# V1_1.net
KiCad netlist of a schematic drawn in Altium Designer
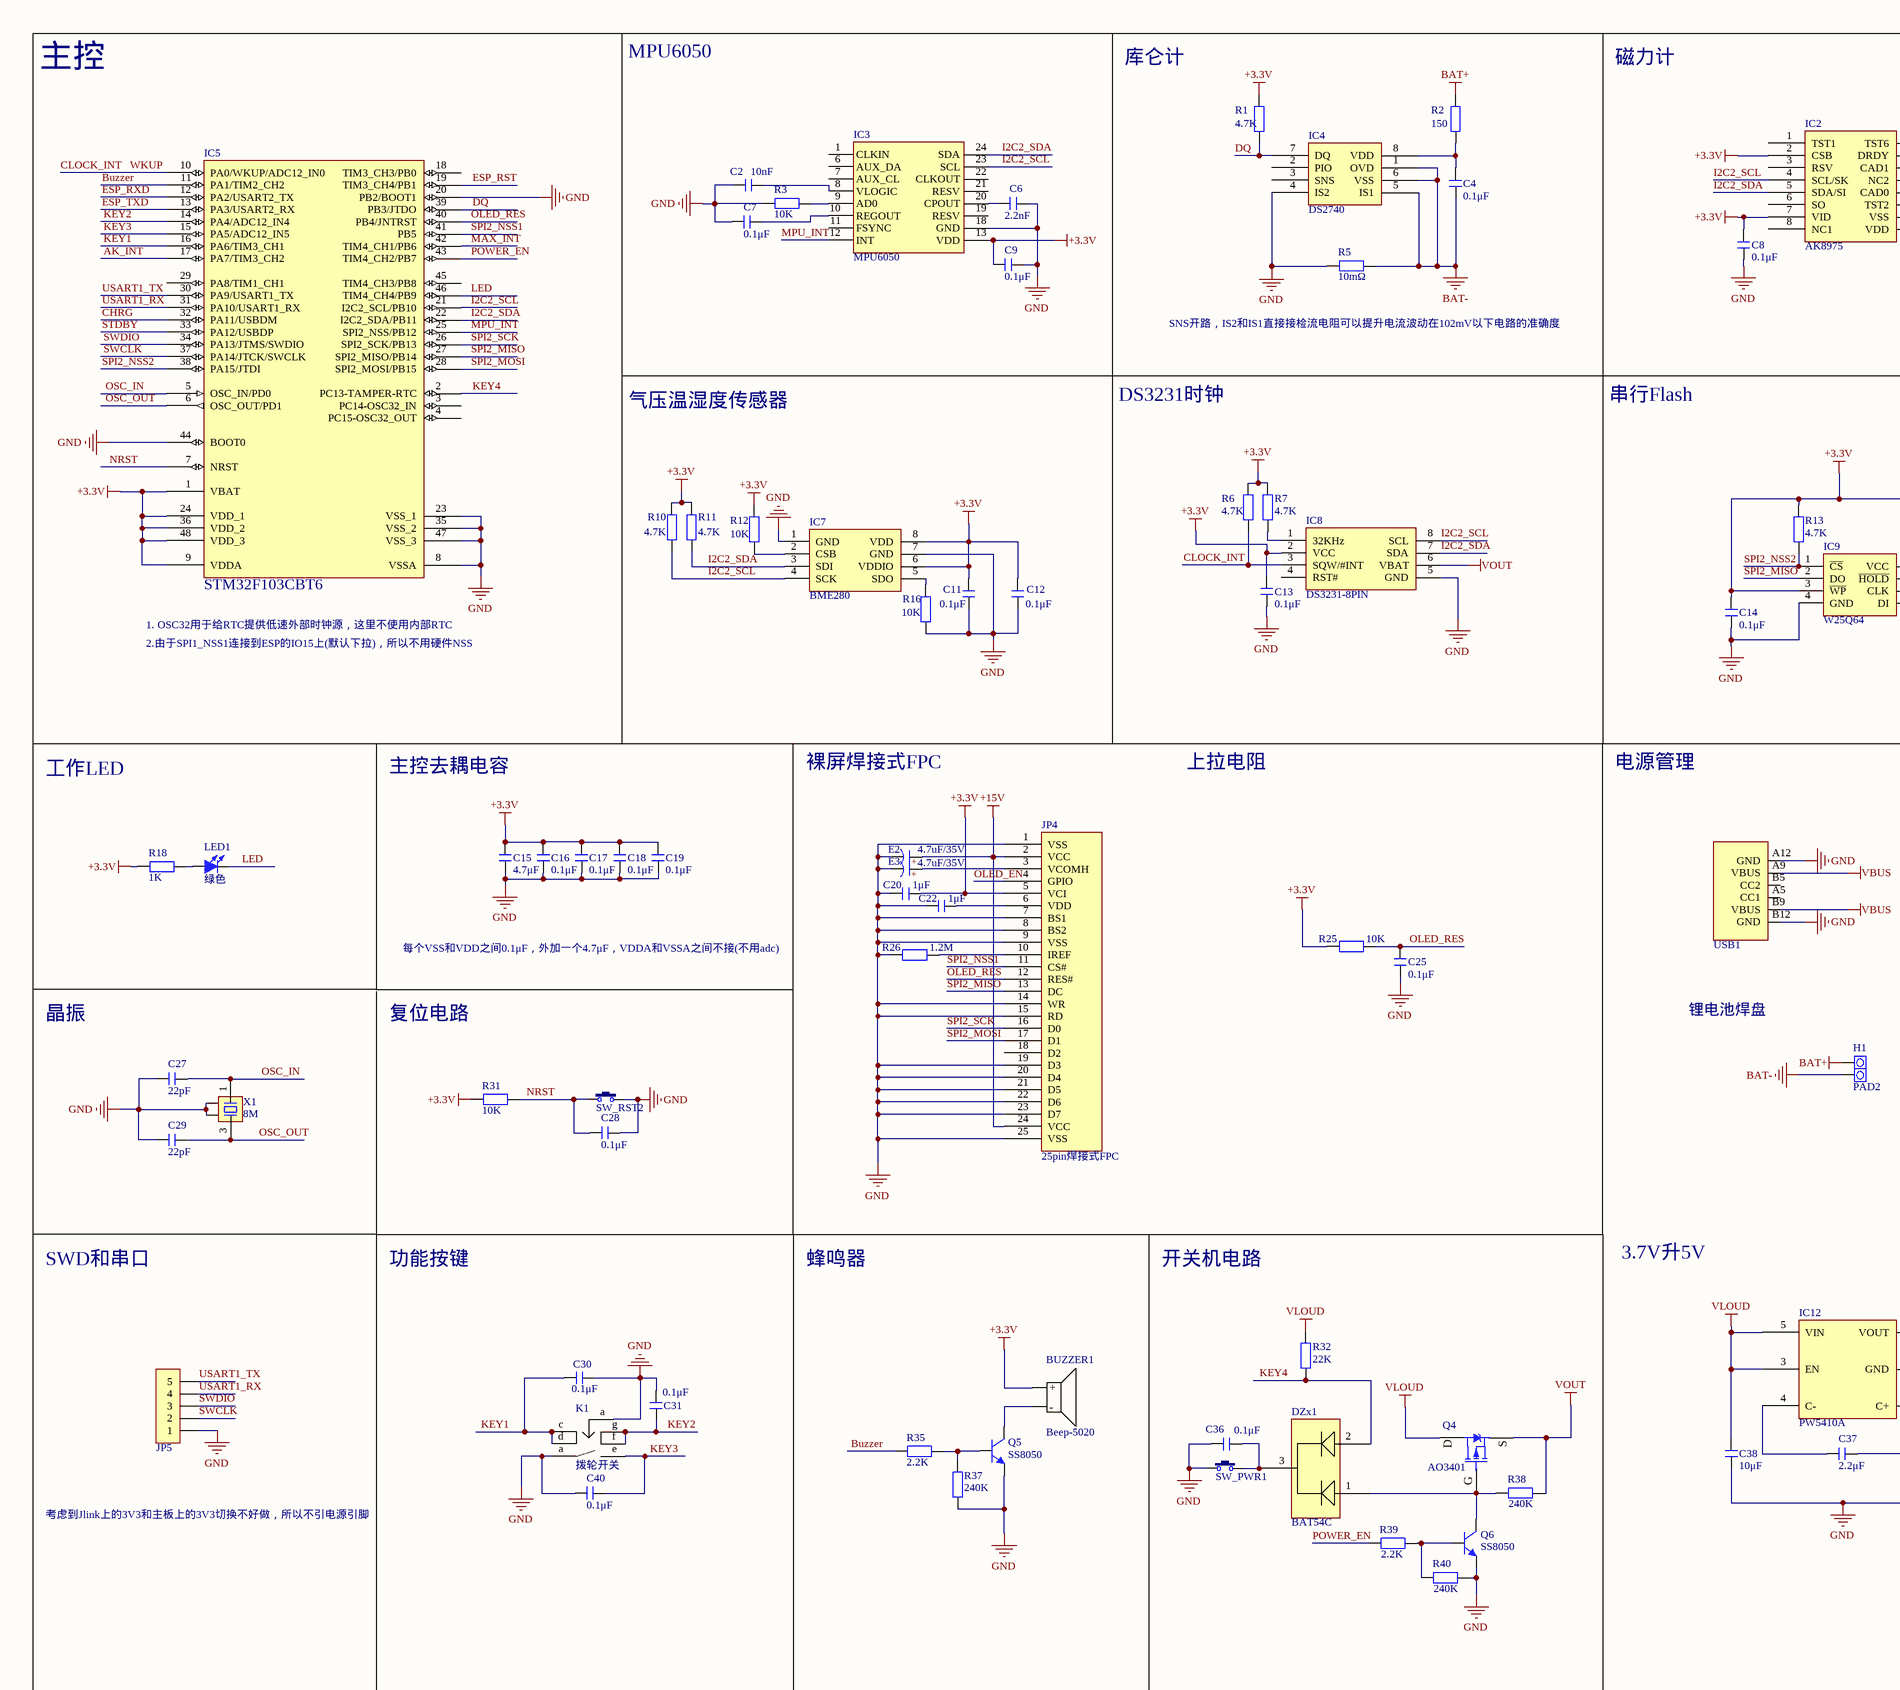
[diagram p0: V1.1.SchDoc, left]
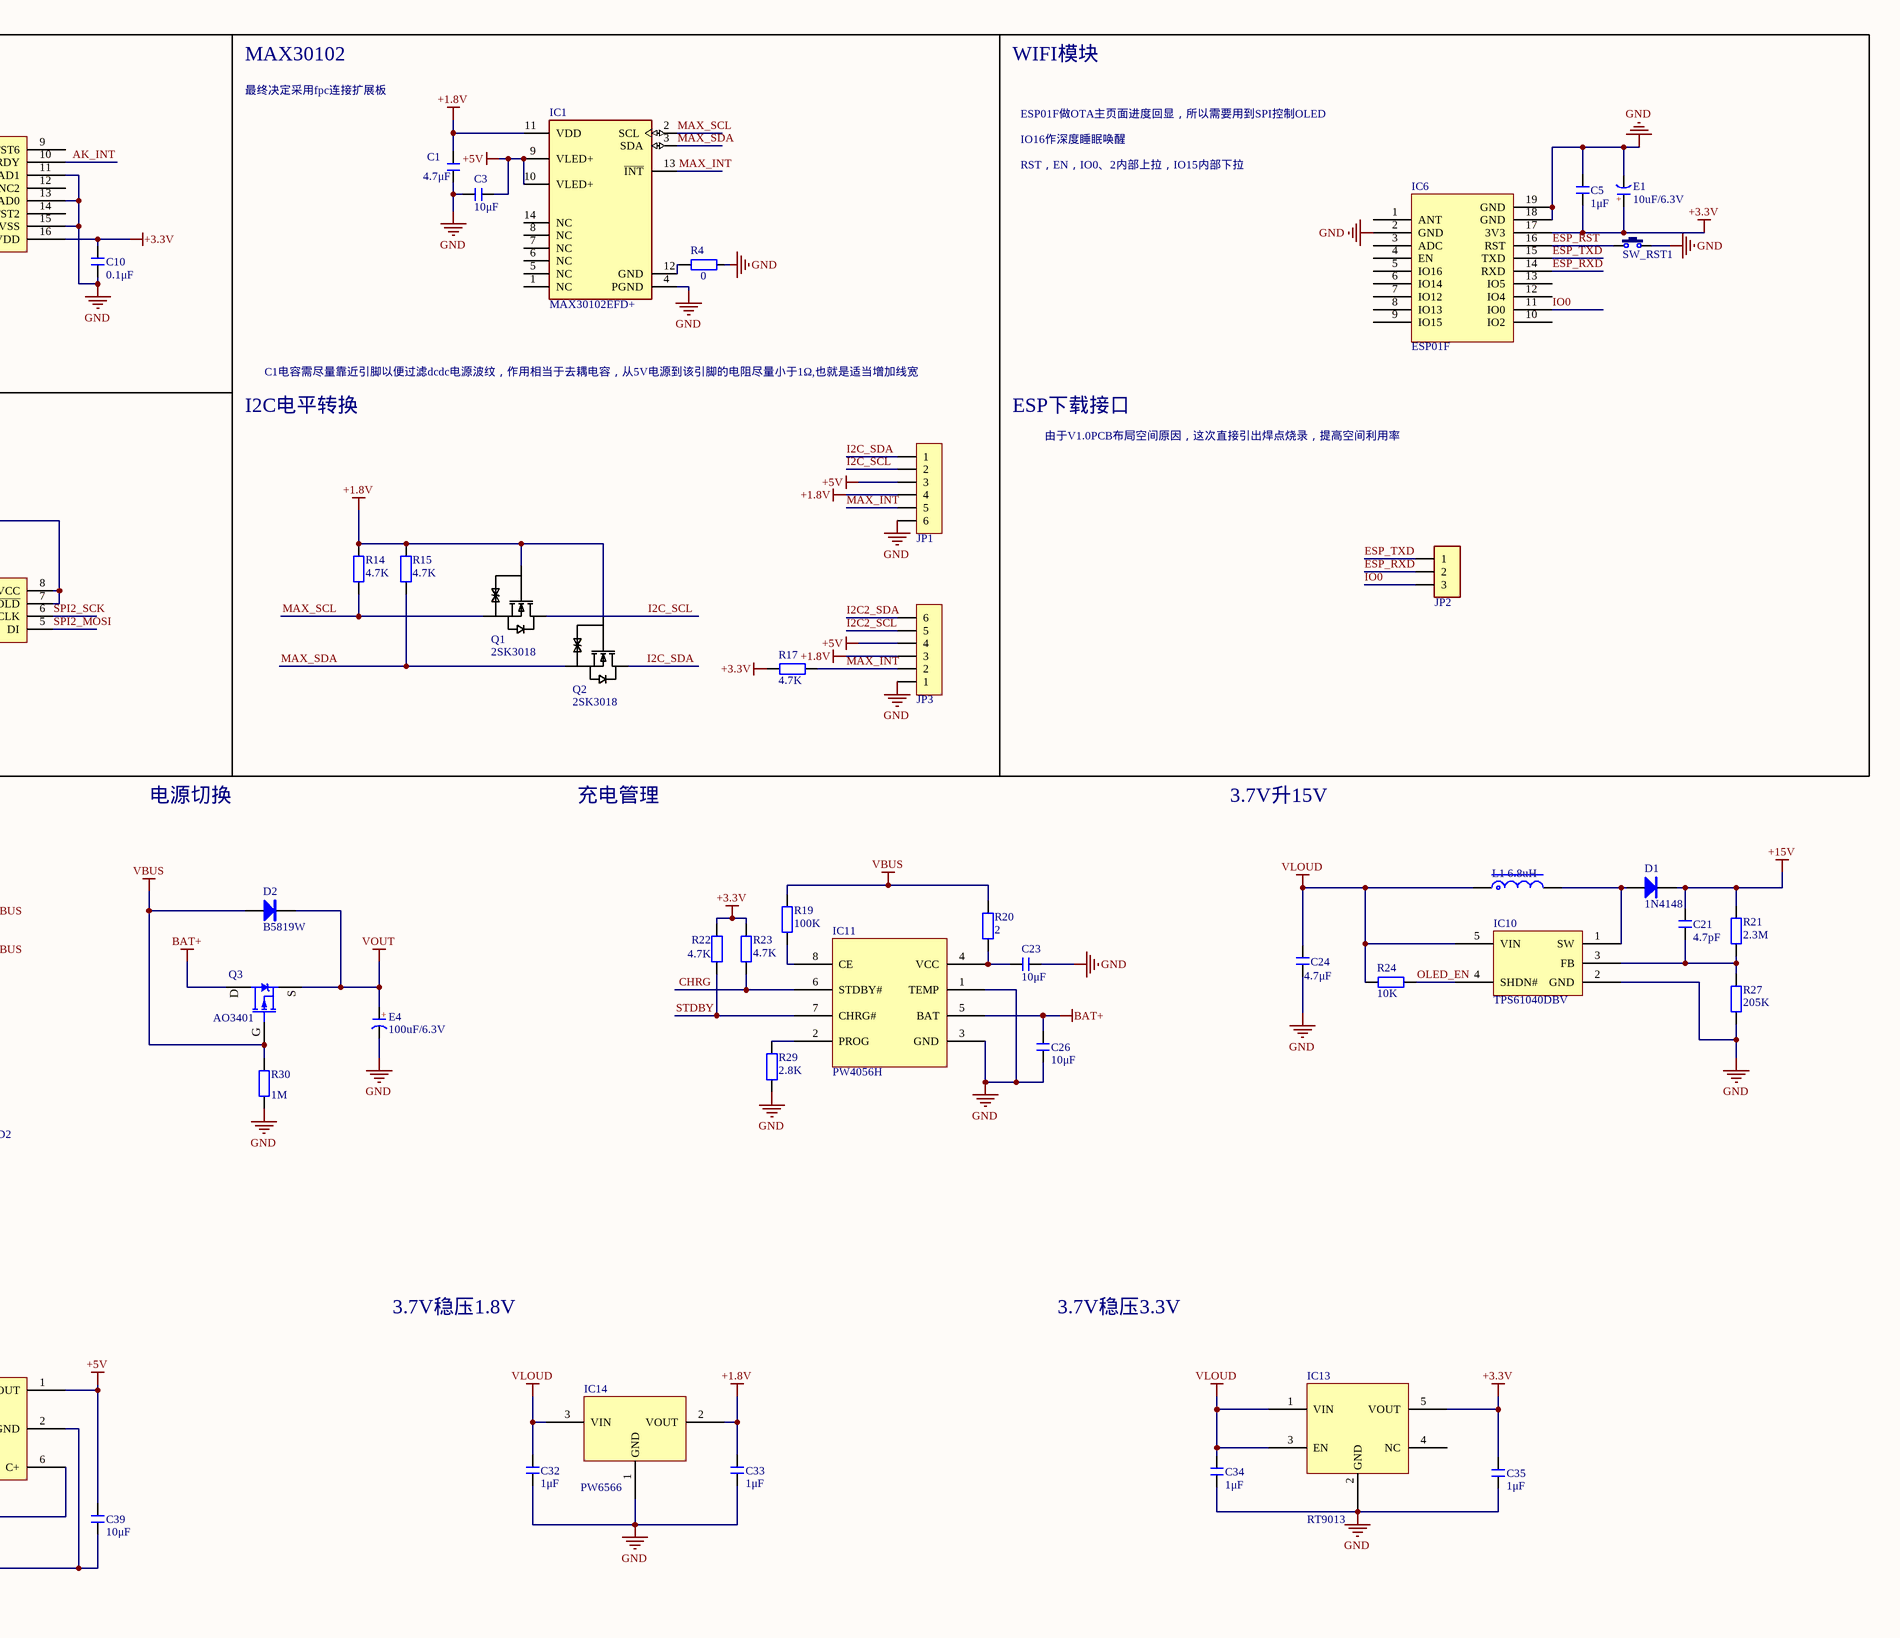
[diagram p1: V1.1.SchDoc, right]

(export (version "E")
  (design (tool "Eeschema 10.0.6"))
  (components
    (comp (ref "BUZZER1")
      (value "Beep-5020")
      (footprint "5020BUZZER")
      (description "贴片蜂鸣器5020最小封装")
      (libsource (lib "STM32_Watch") (part "Beep-5020"))
    )
    (comp (ref "C1")
      (value "4.7μF")
      (footprint "C 0603_L")
      (description "无极性贴片电容")
      (fields (field (name "版权归属") "源创客"))
      (libsource (lib "STM32_Watch") (part "C"))
    )
    (comp (ref "C2")
      (value "10nF")
      (footprint "C 0603_L")
      (description "无极性贴片电容")
      (fields (field (name "版权归属") "源创客"))
      (libsource (lib "STM32_Watch") (part "C"))
    )
    (comp (ref "C3")
      (value "10μF")
      (footprint "C 0603_L")
      (description "无极性贴片电容")
      (fields (field (name "版权归属") "源创客"))
      (libsource (lib "STM32_Watch") (part "C"))
    )
    (comp (ref "C4")
      (value "0.1μF")
      (footprint "C 0603_L")
      (description "无极性贴片电容")
      (fields (field (name "版权归属") "源创客"))
      (libsource (lib "STM32_Watch") (part "C"))
    )
    (comp (ref "C5")
      (value "1μF")
      (footprint "C 0603_L")
      (description "无极性贴片电容")
      (fields (field (name "版权归属") "源创客"))
      (libsource (lib "STM32_Watch") (part "C"))
    )
    (comp (ref "C6")
      (value "2.2nF")
      (footprint "C 0603_L")
      (description "无极性贴片电容")
      (fields (field (name "版权归属") "源创客"))
      (libsource (lib "STM32_Watch") (part "C"))
    )
    (comp (ref "C7")
      (value "0.1μF")
      (footprint "C 0603_L")
      (description "无极性贴片电容")
      (fields (field (name "版权归属") "源创客"))
      (libsource (lib "STM32_Watch") (part "C"))
    )
    (comp (ref "C8")
      (value "0.1μF")
      (footprint "C 0603_L")
      (description "无极性贴片电容")
      (fields (field (name "版权归属") "源创客"))
      (libsource (lib "STM32_Watch") (part "C"))
    )
    (comp (ref "C9")
      (value "0.1μF")
      (footprint "C 0603_L")
      (description "无极性贴片电容")
      (fields (field (name "版权归属") "源创客"))
      (libsource (lib "STM32_Watch") (part "C"))
    )
    (comp (ref "C10")
      (value "0.1μF")
      (footprint "C 0603_L")
      (description "无极性贴片电容")
      (fields (field (name "版权归属") "源创客"))
      (libsource (lib "STM32_Watch") (part "C"))
    )
    (comp (ref "C11")
      (value "0.1μF")
      (footprint "C 0603_L")
      (description "无极性贴片电容")
      (fields (field (name "版权归属") "源创客"))
      (libsource (lib "STM32_Watch") (part "C"))
    )
    (comp (ref "C12")
      (value "0.1μF")
      (footprint "C 0603_L")
      (description "无极性贴片电容")
      (fields (field (name "版权归属") "源创客"))
      (libsource (lib "STM32_Watch") (part "C"))
    )
    (comp (ref "C13")
      (value "0.1μF")
      (footprint "C 0603_L")
      (description "无极性贴片电容")
      (fields (field (name "版权归属") "源创客"))
      (libsource (lib "STM32_Watch") (part "C"))
    )
    (comp (ref "C14")
      (value "0.1μF")
      (footprint "C 0603_L")
      (description "无极性贴片电容")
      (fields (field (name "版权归属") "源创客"))
      (libsource (lib "STM32_Watch") (part "C"))
    )
    (comp (ref "C15")
      (value "4.7μF")
      (footprint "C 0603_L")
      (description "无极性贴片电容")
      (fields (field (name "版权归属") "源创客"))
      (libsource (lib "STM32_Watch") (part "C"))
    )
    (comp (ref "C16")
      (value "0.1μF")
      (footprint "C 0603_L")
      (description "无极性贴片电容")
      (fields (field (name "版权归属") "源创客"))
      (libsource (lib "STM32_Watch") (part "C"))
    )
    (comp (ref "C17")
      (value "0.1μF")
      (footprint "C 0603_L")
      (description "无极性贴片电容")
      (fields (field (name "版权归属") "源创客"))
      (libsource (lib "STM32_Watch") (part "C"))
    )
    (comp (ref "C18")
      (value "0.1μF")
      (footprint "C 0603_L")
      (description "无极性贴片电容")
      (fields (field (name "版权归属") "源创客"))
      (libsource (lib "STM32_Watch") (part "C"))
    )
    (comp (ref "C19")
      (value "0.1μF")
      (footprint "C 0603_L")
      (description "无极性贴片电容")
      (fields (field (name "版权归属") "源创客"))
      (libsource (lib "STM32_Watch") (part "C"))
    )
    (comp (ref "C20")
      (value "1μF")
      (footprint "C 0603_L")
      (description "无极性贴片电容")
      (fields (field (name "版权归属") "源创客"))
      (libsource (lib "STM32_Watch") (part "C"))
    )
    (comp (ref "C21")
      (value "4.7pF")
      (footprint "C 0603_L")
      (description "无极性贴片电容")
      (fields (field (name "版权归属") "源创客"))
      (libsource (lib "STM32_Watch") (part "C"))
    )
    (comp (ref "C22")
      (value "1μF")
      (footprint "C 0603_L")
      (description "无极性贴片电容")
      (fields (field (name "版权归属") "源创客"))
      (libsource (lib "STM32_Watch") (part "C"))
    )
    (comp (ref "C23")
      (value "10μF")
      (footprint "C 0603_L")
      (description "无极性贴片电容")
      (fields (field (name "版权归属") "源创客"))
      (libsource (lib "STM32_Watch") (part "C"))
    )
    (comp (ref "C24")
      (value "4.7μF")
      (footprint "C 0603_L")
      (description "无极性贴片电容")
      (fields (field (name "版权归属") "源创客"))
      (libsource (lib "STM32_Watch") (part "C"))
    )
    (comp (ref "C25")
      (value "0.1μF")
      (footprint "C 0603_L")
      (description "无极性贴片电容")
      (fields (field (name "版权归属") "源创客"))
      (libsource (lib "STM32_Watch") (part "C"))
    )
    (comp (ref "C26")
      (value "10μF")
      (footprint "C 0603_L")
      (description "无极性贴片电容")
      (fields (field (name "版权归属") "源创客"))
      (libsource (lib "STM32_Watch") (part "C"))
    )
    (comp (ref "C27")
      (value "22pF")
      (footprint "C 0603_L")
      (description "无极性贴片电容")
      (fields (field (name "版权归属") "源创客"))
      (libsource (lib "STM32_Watch") (part "C"))
    )
    (comp (ref "C28")
      (value "0.1μF")
      (footprint "C 0603_L")
      (description "无极性贴片电容")
      (fields (field (name "版权归属") "源创客"))
      (libsource (lib "STM32_Watch") (part "C"))
    )
    (comp (ref "C29")
      (value "22pF")
      (footprint "C 0603_L")
      (description "无极性贴片电容")
      (fields (field (name "版权归属") "源创客"))
      (libsource (lib "STM32_Watch") (part "C"))
    )
    (comp (ref "C30")
      (value "0.1μF")
      (footprint "C 0603_L")
      (description "无极性贴片电容")
      (fields (field (name "版权归属") "源创客"))
      (libsource (lib "STM32_Watch") (part "C"))
    )
    (comp (ref "C31")
      (value "0.1μF")
      (footprint "C 0603_L")
      (description "无极性贴片电容")
      (fields (field (name "版权归属") "源创客"))
      (libsource (lib "STM32_Watch") (part "C"))
    )
    (comp (ref "C32")
      (value "1μF")
      (footprint "C 0603_L")
      (description "无极性贴片电容")
      (fields (field (name "版权归属") "源创客"))
      (libsource (lib "STM32_Watch") (part "C"))
    )
    (comp (ref "C33")
      (value "1μF")
      (footprint "C 0603_L")
      (description "无极性贴片电容")
      (fields (field (name "版权归属") "源创客"))
      (libsource (lib "STM32_Watch") (part "C"))
    )
    (comp (ref "C34")
      (value "1μF")
      (footprint "C 0603_L")
      (description "无极性贴片电容")
      (fields (field (name "版权归属") "源创客"))
      (libsource (lib "STM32_Watch") (part "C"))
    )
    (comp (ref "C35")
      (value "1μF")
      (footprint "C 0603_L")
      (description "无极性贴片电容")
      (fields (field (name "版权归属") "源创客"))
      (libsource (lib "STM32_Watch") (part "C"))
    )
    (comp (ref "C36")
      (value "0.1μF")
      (footprint "C 0603_L")
      (description "无极性贴片电容")
      (fields (field (name "版权归属") "源创客"))
      (libsource (lib "STM32_Watch") (part "C"))
    )
    (comp (ref "C37")
      (value "2.2μF")
      (footprint "C 0603_L")
      (description "无极性贴片电容")
      (fields (field (name "版权归属") "源创客"))
      (libsource (lib "STM32_Watch") (part "C"))
    )
    (comp (ref "C38")
      (value "10μF")
      (footprint "C 0603_L")
      (description "无极性贴片电容")
      (fields (field (name "版权归属") "源创客"))
      (libsource (lib "STM32_Watch") (part "C"))
    )
    (comp (ref "C39")
      (value "10μF")
      (footprint "C 0603_L")
      (description "无极性贴片电容")
      (fields (field (name "版权归属") "源创客"))
      (libsource (lib "STM32_Watch") (part "C"))
    )
    (comp (ref "C40")
      (value "0.1μF")
      (footprint "C 0603_L")
      (description "无极性贴片电容")
      (fields (field (name "版权归属") "源创客"))
      (libsource (lib "STM32_Watch") (part "C"))
    )
    (comp (ref "D1")
      (value "1N4148")
      (footprint "SOD-123")
      (description "高速开关二极管")
      (fields (field (name "版权归属") "源创客"))
      (libsource (lib "STM32_Watch") (part "1N4148"))
    )
    (comp (ref "D2")
      (value "B5819W")
      (footprint "SOD-123")
      (description "肖特基二极管")
      (fields (field (name "版权归属") "源创客"))
      (libsource (lib "STM32_Watch") (part "B5819W"))
    )
    (comp (ref "DZx1")
      (value "BAT54C")
      (footprint "SOT23-3N")
      (description "双肖特基，共阴极")
      (libsource (lib "STM32_Watch") (part "BAT54C"))
    )
    (comp (ref "E1")
      (value "10uF/6.3V")
      (footprint "CD A(3216)")
      (description "贴片钽电容")
      (fields (field (name "版权归属") "源创客"))
      (libsource (lib "3.1   - 电阻-电容-电感") (part "C-CD"))
    )
    (comp (ref "E2")
      (value "4.7uF/35V")
      (footprint "CD A(3216)")
      (description "贴片钽电容")
      (fields (field (name "版权归属") "源创客"))
      (libsource (lib "") (part "C-CD_1"))
    )
    (comp (ref "E3")
      (value "4.7uF/35V")
      (footprint "CD A(3216)")
      (description "贴片钽电容")
      (fields (field (name "版权归属") "源创客"))
      (libsource (lib "") (part "C-CD_1"))
    )
    (comp (ref "E4")
      (value "100uF/6.3V")
      (footprint "CD A(3216)")
      (description "贴片钽电容")
      (fields (field (name "版权归属") "源创客"))
      (libsource (lib "3.1   - 电阻-电容-电感") (part "C-CD"))
    )
    (comp (ref "H1")
      (value "PAD2")
      (footprint "CHARGE_PAD")
      (description "引线焊盘")
      (fields (field (name "版权归属") "源创客"))
      (libsource (lib "STM32_Watch") (part "PAD2"))
    )
    (comp (ref "IC1")
      (value "MAX30102EFD+")
      (footprint "FP-F143A5-1-MFG")
      (description "IC SENSOR OXIMETER/HEARTRATE")
      (fields
        (field (name "MANUFACTURER") "Maxim Integrated")
        (field (name "OCTOPART") "https://octopart.com/max30102efd%2B-maxim+integrated-59568799")
      )
      (libsource (lib "STM32_Watch") (part "MAX30102"))
    )
    (comp (ref "IC2")
      (value "AK8975")
      (footprint "QFN16")
      (description "采用高灵敏度霍尔传感器技术的三轴电子罗盘IC。\r\n最适合步行城市导航，用于手机和其他便携式设备")
      (libsource (lib "STM32_Watch") (part "AK8975"))
    )
    (comp (ref "IC3")
      (value "MPU6050")
      (footprint "QFN24 4x4_M")
      (description "陀螺仪")
      (libsource (lib "STM32_Watch") (part "MPU6050"))
    )
    (comp (ref "IC4")
      (value "DS2740")
      (footprint "MSOP8_L")
      (description "高精度库仑计")
      (libsource (lib "STM32_Watch") (part "DS2740"))
    )
    (comp (ref "IC5")
      (value "STM32F103CBT6")
      (footprint "LQFP48 7X7_M")
      (description "Flash:128/RAM:20/IO:48")
      (fields (field (name "版权归属") "源创客"))
      (libsource (lib "STM32_Watch") (part "STM32F103CB"))
    )
    (comp (ref "IC6") (value "ESP01F") (footprint "ESP-01F") (libsource (lib "STM32_Watch") (part "ESP01F")))
    (comp (ref "IC7")
      (value "BME280")
      (footprint "BME280")
      (description "气压，湿度，温度传感器")
      (libsource (lib "STM32_Watch") (part "BME280"))
    )
    (comp (ref "IC8")
      (value "DS3231-8PIN")
      (footprint "SOP8_N")
      (libsource (lib "STM32_Watch") (part "DS3231-8PIN"))
    )
    (comp (ref "IC9")
      (value "W25Q64")
      (footprint "SOP8W_N")
      (description "外置Flash")
      (fields (field (name "版权归属") "源创客"))
      (libsource (lib "1.1   - IC芯片") (part "W25Qxx"))
    )
    (comp (ref "IC10")
      (value "TPS61040DBV")
      (footprint "SOT23-5L")
      (description "28V、400mA 开关升压转换器，适用于 LCD 和白光 LED")
      (libsource (lib "STM32_Watch") (part "TPS61040DBV"))
    )
    (comp (ref "IC11")
      (value "PW4056H")
      (footprint "SOP-8_L4.9-W3.9-P1.27-LS6.0-BL-EP3.1")
      (description "PW4056H 是一款完整的采用恒定电流/恒定电压的高压、大电流、单节鲤离子电池线性充电IC，最高耐压可达 28V，6.5V 自动过压保护，充电电流可达 1A。")
      (libsource (lib "STM32_Watch") (part "PW4056H"))
    )
    (comp (ref "IC12")
      (value "PW5410A")
      (footprint "SOT23-6")
      (description "低噪声，恒频 1.2MHZ，输入电压范围2.7v-5v，5v固定输出电压，输出电流250mA的DCDC升压")
      (libsource (lib "STM32_Watch") (part "PW5410A"))
    )
    (comp (ref "IC13")
      (value "RT9013")
      (footprint "SOT23-5L")
      (libsource (lib "STM32_Watch") (part "RT9013"))
    )
    (comp (ref "IC14")
      (value "PW6566")
      (footprint "SOT23-3L")
      (description "PW6566 系列是使用 CMOS 技术开发的低压差，高精度 输出电压，低消耗电流正电压型电压稳压器")
      (libsource (lib "STM32_Watch") (part "PW6566"))
    )
    (comp (ref "JP1")
      (value "FPC1.0-6P")
      (footprint "FPC0.5 2H-WS-6P")
      (description "FPC连接器")
      (fields (field (name "版权归属") "源创客"))
      (libsource (lib "STM32_Watch") (part "FPC-6P"))
    )
    (comp (ref "JP2")
      (value "HDR-1X3")
      (footprint "TEST_POINT_3")
      (description "3P接插件")
      (fields (field (name "版权归属") "源创客"))
      (libsource (lib "STM32_Watch") (part "Header 3"))
    )
    (comp (ref "JP3")
      (value "FPC1.0-6P")
      (footprint "FPC0.5 2H-WS-6P")
      (description "FPC连接器")
      (fields (field (name "版权归属") "源创客"))
      (libsource (lib "") (part "FPC-6P_1"))
    )
    (comp (ref "JP4")
      (value "25pin焊接式FPC")
      (footprint "25pin焊接式FPC")
      (libsource (lib "STM32_Watch") (part "25pin焊接式FPC"))
    )
    (comp (ref "JP5")
      (value "HDR-1X5")
      (footprint "TEST_POINT_5")
      (description "5P接插件")
      (fields (field (name "版权归属") "源创客"))
      (libsource (lib "STM32_Watch") (part "Header 5"))
    )
    (comp (ref "K1") (value "拨轮开关") (footprint "拨轮开关") (libsource (lib "STM32_Watch") (part "拨轮开关")))
    (comp (ref "L1")
      (value "6.8uH")
      (footprint "NR3015")
      (description "NR磁胶电感")
      (fields (field (name "版权归属") "源创客"))
      (libsource (lib "STM32_Watch") (part "L-NR"))
    )
    (comp (ref "LED1")
      (value "绿色")
      (footprint "LED 0603G")
      (description "贴片LED")
      (fields (field (name "版权归属") "源创客"))
      (libsource (lib "STM32_Watch") (part "LED-SMD"))
    )
    (comp (ref "Q1")
      (value "2SK3018")
      (footprint "SOT23-3L")
      (fields (field (name "MANUFACTURER") "TWGMC(台湾迪嘉)"))
      (libsource (lib "STM32_Watch") (part "2SK3018"))
    )
    (comp (ref "Q2")
      (value "2SK3018")
      (footprint "SOT23-3L")
      (fields (field (name "MANUFACTURER") "TWGMC(台湾迪嘉)"))
      (libsource (lib "STM32_Watch") (part "2SK3018"))
    )
    (comp (ref "Q3")
      (value "AO3401")
      (footprint "SOT23-3N")
      (description "P沟道场效应管")
      (fields (field (name "版权归属") "源创客"))
      (libsource (lib "STM32_Watch") (part "AO3401"))
    )
    (comp (ref "Q4")
      (value "AO3401")
      (footprint "SOT23-3N")
      (description "P沟道场效应管")
      (fields (field (name "版权归属") "源创客"))
      (libsource (lib "STM32_Watch") (part "AO3401"))
    )
    (comp (ref "Q5")
      (value "SS8050")
      (footprint "SOT23-3N")
      (description "高频放大-NPN型")
      (fields (field (name "版权归属") "源创客"))
      (libsource (lib "STM32_Watch") (part "8050-SMD"))
    )
    (comp (ref "Q6")
      (value "SS8050")
      (footprint "SOT23-3N")
      (description "高频放大-NPN型")
      (fields (field (name "版权归属") "源创客"))
      (libsource (lib "STM32_Watch") (part "8050-SMD"))
    )
    (comp (ref "R1")
      (value "4.7K")
      (footprint "R 0603_L")
      (description "贴片电阻")
      (fields (field (name "版权归属") "源创客"))
      (libsource (lib "STM32_Watch") (part "R"))
    )
    (comp (ref "R2")
      (value "150")
      (footprint "R 0603_L")
      (description "贴片电阻")
      (fields (field (name "版权归属") "源创客"))
      (libsource (lib "STM32_Watch") (part "R"))
    )
    (comp (ref "R3")
      (value "10K")
      (footprint "R 0603_L")
      (description "贴片电阻")
      (fields (field (name "版权归属") "源创客"))
      (libsource (lib "STM32_Watch") (part "R"))
    )
    (comp (ref "R4")
      (value "0")
      (footprint "R 0603_L")
      (description "贴片电阻")
      (fields (field (name "版权归属") "源创客"))
      (libsource (lib "STM32_Watch") (part "R"))
    )
    (comp (ref "R5")
      (value "10mΩ")
      (footprint "R 0603_L")
      (description "贴片电阻")
      (fields (field (name "版权归属") "源创客"))
      (libsource (lib "STM32_Watch") (part "R"))
    )
    (comp (ref "R6")
      (value "4.7K")
      (footprint "R 0603_L")
      (description "贴片电阻")
      (fields (field (name "版权归属") "源创客"))
      (libsource (lib "STM32_Watch") (part "R"))
    )
    (comp (ref "R7")
      (value "4.7K")
      (footprint "R 0603_L")
      (description "贴片电阻")
      (fields (field (name "版权归属") "源创客"))
      (libsource (lib "STM32_Watch") (part "R"))
    )
    (comp (ref "R10")
      (value "4.7K")
      (footprint "R 0603_L")
      (description "贴片电阻")
      (fields (field (name "版权归属") "源创客"))
      (libsource (lib "STM32_Watch") (part "R"))
    )
    (comp (ref "R11")
      (value "4.7K")
      (footprint "R 0603_L")
      (description "贴片电阻")
      (fields (field (name "版权归属") "源创客"))
      (libsource (lib "STM32_Watch") (part "R"))
    )
    (comp (ref "R12")
      (value "10K")
      (footprint "R 0603_L")
      (description "贴片电阻")
      (fields (field (name "版权归属") "源创客"))
      (libsource (lib "STM32_Watch") (part "R"))
    )
    (comp (ref "R13")
      (value "4.7K")
      (footprint "R 0603_L")
      (description "贴片电阻")
      (fields (field (name "版权归属") "源创客"))
      (libsource (lib "STM32_Watch") (part "R"))
    )
    (comp (ref "R14")
      (value "4.7K")
      (footprint "R 0603_L")
      (description "贴片电阻")
      (fields (field (name "版权归属") "源创客"))
      (libsource (lib "STM32_Watch") (part "R"))
    )
    (comp (ref "R15")
      (value "4.7K")
      (footprint "R 0603_L")
      (description "贴片电阻")
      (fields (field (name "版权归属") "源创客"))
      (libsource (lib "STM32_Watch") (part "R"))
    )
    (comp (ref "R16")
      (value "10K")
      (footprint "R 0603_L")
      (description "贴片电阻")
      (fields (field (name "版权归属") "源创客"))
      (libsource (lib "STM32_Watch") (part "R"))
    )
    (comp (ref "R17")
      (value "4.7K")
      (footprint "R 0603_L")
      (description "贴片电阻")
      (fields (field (name "版权归属") "源创客"))
      (libsource (lib "STM32_Watch") (part "R"))
    )
    (comp (ref "R18")
      (value "1K")
      (footprint "R 0603_L")
      (description "贴片电阻")
      (fields (field (name "版权归属") "源创客"))
      (libsource (lib "STM32_Watch") (part "R"))
    )
    (comp (ref "R19")
      (value "100K")
      (footprint "R 0603_L")
      (description "贴片电阻")
      (fields (field (name "版权归属") "源创客"))
      (libsource (lib "STM32_Watch") (part "R"))
    )
    (comp (ref "R20")
      (value "2")
      (footprint "R 0603_L")
      (description "贴片电阻")
      (fields (field (name "版权归属") "源创客"))
      (libsource (lib "STM32_Watch") (part "R"))
    )
    (comp (ref "R21")
      (value "2.3M")
      (footprint "R 0603_L")
      (description "贴片电阻")
      (fields (field (name "版权归属") "源创客"))
      (libsource (lib "STM32_Watch") (part "R"))
    )
    (comp (ref "R22")
      (value "4.7K")
      (footprint "R 0603_L")
      (description "贴片电阻")
      (fields (field (name "版权归属") "源创客"))
      (libsource (lib "STM32_Watch") (part "R"))
    )
    (comp (ref "R23")
      (value "4.7K")
      (footprint "R 0603_L")
      (description "贴片电阻")
      (fields (field (name "版权归属") "源创客"))
      (libsource (lib "STM32_Watch") (part "R"))
    )
    (comp (ref "R24")
      (value "10K")
      (footprint "R 0603_L")
      (description "贴片电阻")
      (fields (field (name "版权归属") "源创客"))
      (libsource (lib "STM32_Watch") (part "R"))
    )
    (comp (ref "R25")
      (value "10K")
      (footprint "R 0603_L")
      (description "贴片电阻")
      (fields (field (name "版权归属") "源创客"))
      (libsource (lib "STM32_Watch") (part "R"))
    )
    (comp (ref "R26")
      (value "1.2M")
      (footprint "R 0603_L")
      (description "贴片电阻")
      (fields (field (name "版权归属") "源创客"))
      (libsource (lib "STM32_Watch") (part "R"))
    )
    (comp (ref "R27")
      (value "205K")
      (footprint "R 0603_L")
      (description "贴片电阻")
      (fields (field (name "版权归属") "源创客"))
      (libsource (lib "STM32_Watch") (part "R"))
    )
    (comp (ref "R29")
      (value "2.8K")
      (footprint "R 0603_L")
      (description "贴片电阻")
      (fields (field (name "版权归属") "源创客"))
      (libsource (lib "STM32_Watch") (part "R"))
    )
    (comp (ref "R30")
      (value "1M")
      (footprint "R 0603_L")
      (description "贴片电阻")
      (fields (field (name "版权归属") "源创客"))
      (libsource (lib "STM32_Watch") (part "R"))
    )
    (comp (ref "R31")
      (value "10K")
      (footprint "R 0603_L")
      (description "贴片电阻")
      (fields (field (name "版权归属") "源创客"))
      (libsource (lib "STM32_Watch") (part "R"))
    )
    (comp (ref "R32")
      (value "22K")
      (footprint "R 0603_L")
      (description "贴片电阻")
      (fields (field (name "版权归属") "源创客"))
      (libsource (lib "STM32_Watch") (part "R"))
    )
    (comp (ref "R35")
      (value "2.2K")
      (footprint "R 0603_L")
      (description "贴片电阻")
      (fields (field (name "版权归属") "源创客"))
      (libsource (lib "STM32_Watch") (part "R"))
    )
    (comp (ref "R37")
      (value "240K")
      (footprint "R 0603_L")
      (description "贴片电阻")
      (fields (field (name "版权归属") "源创客"))
      (libsource (lib "STM32_Watch") (part "R"))
    )
    (comp (ref "R38")
      (value "240K")
      (footprint "R 0603_L")
      (description "贴片电阻")
      (fields (field (name "版权归属") "源创客"))
      (libsource (lib "STM32_Watch") (part "R"))
    )
    (comp (ref "R39")
      (value "2.2K")
      (footprint "R 0603_L")
      (description "贴片电阻")
      (fields (field (name "版权归属") "源创客"))
      (libsource (lib "STM32_Watch") (part "R"))
    )
    (comp (ref "R40")
      (value "240K")
      (footprint "R 0603_L")
      (description "贴片电阻")
      (fields (field (name "版权归属") "源创客"))
      (libsource (lib "STM32_Watch") (part "R"))
    )
    (comp (ref "SW_PWR1")
      (value "3")
      (footprint "KEY-SMD_UK-B0264-SP25Y")
      (description "2x4x3.5轻触开关")
      (fields (field (name "版权归属") "源创客"))
      (libsource (lib "STM32_Watch") (part "TSW 2x4x3.5"))
    )
    (comp (ref "SW_RST1")
      (value "3x4x2")
      (footprint "SW-SMD_L4.0-W3.0-LS4.6")
      (description "3x4x2开关")
      (fields (field (name "版权归属") "源创客"))
      (libsource (lib "STM32_Watch") (part "TSW 3x4x2"))
    )
    (comp (ref "SW_RST2")
      (value "3x4x2")
      (footprint "SW-SMD_L4.0-W3.0-LS4.6")
      (description "3x4x2开关")
      (fields (field (name "版权归属") "源创客"))
      (libsource (lib "STM32_Watch") (part "TSW 3x4x2"))
    )
    (comp (ref "USB1")
      (value "918-418K2023S40006")
      (footprint "USB-C-SMD_918-418K2023S40006")
      (description "连接器类型:Type-C;标准:USB 3.1;公母:母座;触点数量:6;端口数量:1;安装方式:卧贴;额定电流 - 电源:-;工作温度范围:-40℃~+85℃;")
      (fields (field (name "MANUFACTURER") "精拓金"))
      (libsource (lib "STM32_Watch") (part "TYPE-C 6PIN"))
    )
    (comp (ref "X1")
      (value "8M")
      (footprint "OSC 3225-4P")
      (description "4脚无源晶振")
      (fields (field (name "版权归属") "源创客"))
      (libsource (lib "STM32_Watch") (part "XTAL-4P"))
    )
  )
  (nets
    (net (code "1") (name "+1.8V") (class "Default")
      (node (ref "C1") (pin "1") (pinfunction "1_1") (pintype "passive"))
      (node (ref "C33") (pin "1") (pinfunction "1_1") (pintype "passive"))
      (node (ref "IC1") (pin "11") (pinfunction "VDD_11") (pintype "power_in"))
      (node (ref "IC14") (pin "2") (pinfunction "VOUT_2") (pintype "passive"))
      (node (ref "JP1") (pin "4") (pinfunction "4_4") (pintype "passive"))
      (node (ref "JP3") (pin "3") (pinfunction "3_3") (pintype "passive"))
      (node (ref "Q1") (pin "1") (pinfunction "G_1") (pintype "passive"))
      (node (ref "Q2") (pin "1") (pinfunction "G_1") (pintype "passive"))
      (node (ref "R14") (pin "1") (pinfunction "1_1") (pintype "passive"))
      (node (ref "R15") (pin "1") (pinfunction "1_1") (pintype "passive"))
    )
    (net (code "2") (name "+3.3V") (class "Default")
      (node (ref "BUZZER1") (pin "1") (pinfunction "+_1") (pintype "passive"))
      (node (ref "C10") (pin "2") (pinfunction "2_2") (pintype "passive"))
      (node (ref "C11") (pin "1") (pinfunction "1_1") (pintype "passive"))
      (node (ref "C12") (pin "1") (pinfunction "1_1") (pintype "passive"))
      (node (ref "C13") (pin "1") (pinfunction "1_1") (pintype "passive"))
      (node (ref "C14") (pin "2") (pinfunction "2_2") (pintype "passive"))
      (node (ref "C15") (pin "2") (pinfunction "2_2") (pintype "passive"))
      (node (ref "C16") (pin "2") (pinfunction "2_2") (pintype "passive"))
      (node (ref "C17") (pin "2") (pinfunction "2_2") (pintype "passive"))
      (node (ref "C18") (pin "2") (pinfunction "2_2") (pintype "passive"))
      (node (ref "C19") (pin "2") (pinfunction "2_2") (pintype "passive"))
      (node (ref "C20") (pin "2") (pinfunction "2_2") (pintype "passive"))
      (node (ref "C35") (pin "1") (pinfunction "1_1") (pintype "passive"))
      (node (ref "C5") (pin "1") (pinfunction "1_1") (pintype "passive"))
      (node (ref "C8") (pin "2") (pinfunction "2_2") (pintype "passive"))
      (node (ref "C9") (pin "2") (pinfunction "2_2") (pintype "passive"))
      (node (ref "E1") (pin "1") (pinfunction "A_1") (pintype "passive"))
      (node (ref "IC13") (pin "5") (pinfunction "VOUT_5") (pintype "passive"))
      (node (ref "IC2") (pin "16") (pinfunction "VDD_16") (pintype "passive"))
      (node (ref "IC2") (pin "2") (pinfunction "CSB_2") (pintype "passive"))
      (node (ref "IC2") (pin "7") (pinfunction "VID_7") (pintype "passive"))
      (node (ref "IC3") (pin "13") (pinfunction "VDD_13") (pintype "passive"))
      (node (ref "IC5") (pin "1") (pinfunction "VBAT_1") (pintype "power_in"))
      (node (ref "IC5") (pin "24") (pinfunction "VDD_1_24") (pintype "power_in"))
      (node (ref "IC5") (pin "36") (pinfunction "VDD_2_36") (pintype "power_in"))
      (node (ref "IC5") (pin "48") (pinfunction "VDD_3_48") (pintype "power_in"))
      (node (ref "IC5") (pin "9") (pinfunction "VDDA_9") (pintype "power_in"))
      (node (ref "IC6") (pin "17") (pinfunction "3V3_17") (pintype "passive"))
      (node (ref "IC7") (pin "6") (pinfunction "VDDIO_6") (pintype "passive"))
      (node (ref "IC7") (pin "8") (pinfunction "VDD_8") (pintype "passive"))
      (node (ref "IC8") (pin "2") (pinfunction "VCC_2") (pintype "passive"))
      (node (ref "IC9") (pin "3") (pinfunction "~{WP}_3") (pintype "passive"))
      (node (ref "IC9") (pin "7") (pinfunction "~{HOLD}_7") (pintype "passive"))
      (node (ref "IC9") (pin "8") (pinfunction "VCC_8") (pintype "passive"))
      (node (ref "JP4") (pin "5") (pinfunction "VCI_5") (pintype "passive"))
      (node (ref "R1") (pin "2") (pinfunction "2_2") (pintype "passive"))
      (node (ref "R10") (pin "1") (pinfunction "1_1") (pintype "passive"))
      (node (ref "R11") (pin "1") (pinfunction "1_1") (pintype "passive"))
      (node (ref "R12") (pin "2") (pinfunction "2_2") (pintype "passive"))
      (node (ref "R13") (pin "2") (pinfunction "2_2") (pintype "passive"))
      (node (ref "R17") (pin "2") (pinfunction "2_2") (pintype "passive"))
      (node (ref "R18") (pin "2") (pinfunction "2_2") (pintype "passive"))
      (node (ref "R22") (pin "2") (pinfunction "2_2") (pintype "passive"))
      (node (ref "R23") (pin "2") (pinfunction "2_2") (pintype "passive"))
      (node (ref "R25") (pin "1") (pinfunction "1_1") (pintype "passive"))
      (node (ref "R31") (pin "2") (pinfunction "2_2") (pintype "passive"))
      (node (ref "R6") (pin "1") (pinfunction "1_1") (pintype "passive"))
      (node (ref "R7") (pin "1") (pinfunction "1_1") (pintype "passive"))
    )
    (net (code "3") (name "+5V") (class "Default")
      (node (ref "C3") (pin "2") (pinfunction "2_2") (pintype "passive"))
      (node (ref "C39") (pin "1") (pinfunction "1_1") (pintype "passive"))
      (node (ref "IC1") (pin "10") (pinfunction "VLED+_10") (pintype "power_in"))
      (node (ref "IC1") (pin "9") (pinfunction "VLED+_9") (pintype "power_in"))
      (node (ref "IC12") (pin "1") (pinfunction "VOUT_1") (pintype "passive"))
      (node (ref "JP1") (pin "3") (pinfunction "3_3") (pintype "passive"))
      (node (ref "JP3") (pin "4") (pinfunction "4_4") (pintype "passive"))
    )
    (net (code "4") (name "+15V") (class "Default")
      (node (ref "C21") (pin "2") (pinfunction "2_2") (pintype "passive"))
      (node (ref "D1") (pin "2") (pinfunction "K_2") (pintype "passive"))
      (node (ref "E2") (pin "1") (pinfunction "A_1") (pintype "passive"))
      (node (ref "JP4") (pin "2") (pinfunction "VCC_2") (pintype "passive"))
      (node (ref "JP4") (pin "24") (pinfunction "VCC_24") (pintype "passive"))
      (node (ref "R21") (pin "2") (pinfunction "2_2") (pintype "passive"))
    )
    (net (code "5") (name "/AK_INT") (class "Default")
      (node (ref "IC2") (pin "10") (pinfunction "DRDY_10") (pintype "passive"))
      (node (ref "IC5") (pin "17") (pinfunction "PA7/TIM3_CH2_17") (pintype "bidirectional"))
    )
    (net (code "6") (name "/Buzzer") (class "Default")
      (node (ref "IC5") (pin "11") (pinfunction "PA1/TIM2_CH2_11") (pintype "bidirectional"))
      (node (ref "R35") (pin "1") (pinfunction "1_1") (pintype "passive"))
    )
    (net (code "7") (name "/CHRG") (class "Default")
      (node (ref "IC11") (pin "6") (pinfunction "STDBY#_6") (pintype "passive"))
      (node (ref "IC5") (pin "32") (pinfunction "PA11/USBDM_32") (pintype "bidirectional"))
      (node (ref "R23") (pin "1") (pinfunction "1_1") (pintype "passive"))
    )
    (net (code "8") (name "/CLOCK_INT") (class "Default")
      (node (ref "IC5") (pin "10") (pinfunction "PA0/WKUP/ADC12_IN0_10") (pintype "bidirectional"))
      (node (ref "IC8") (pin "3") (pinfunction "SQW/#INT_3") (pintype "passive"))
      (node (ref "R6") (pin "2") (pinfunction "2_2") (pintype "passive"))
    )
    (net (code "9") (name "/DQ") (class "Default")
      (node (ref "IC4") (pin "7") (pinfunction "DQ_7") (pintype "passive"))
      (node (ref "IC5") (pin "39") (pinfunction "PB3/JTDO_39") (pintype "bidirectional"))
      (node (ref "R1") (pin "1") (pinfunction "1_1") (pintype "passive"))
    )
    (net (code "10") (name "/ESP_RST") (class "Default")
      (node (ref "IC5") (pin "19") (pinfunction "TIM3_CH4/PB1_19") (pintype "bidirectional"))
      (node (ref "IC6") (pin "16") (pinfunction "RST_16") (pintype "passive"))
      (node (ref "SW_RST1") (pin "1") (pinfunction "1_1") (pintype "passive"))
    )
    (net (code "11") (name "/ESP_RXD") (class "Default")
      (node (ref "IC5") (pin "12") (pinfunction "PA2/USART2_TX_12") (pintype "bidirectional"))
      (node (ref "IC6") (pin "14") (pinfunction "RXD_14") (pintype "passive"))
      (node (ref "JP2") (pin "2") (pinfunction "2_2") (pintype "passive"))
    )
    (net (code "12") (name "/ESP_TXD") (class "Default")
      (node (ref "IC5") (pin "13") (pinfunction "PA3/USART2_RX_13") (pintype "bidirectional"))
      (node (ref "IC6") (pin "15") (pinfunction "TXD_15") (pintype "passive"))
      (node (ref "JP2") (pin "1") (pinfunction "1_1") (pintype "passive"))
    )
    (net (code "13") (name "/I2C2_SCL") (class "Default")
      (node (ref "IC2") (pin "4") (pinfunction "SCL/SK_4") (pintype "passive"))
      (node (ref "IC3") (pin "23") (pinfunction "SCL_23") (pintype "passive"))
      (node (ref "IC5") (pin "21") (pinfunction "I2C2_SCL/PB10_21") (pintype "bidirectional"))
      (node (ref "IC7") (pin "4") (pinfunction "SCK_4") (pintype "passive"))
      (node (ref "IC8") (pin "8") (pinfunction "SCL_8") (pintype "passive"))
      (node (ref "JP3") (pin "5") (pinfunction "5_5") (pintype "passive"))
      (node (ref "R10") (pin "2") (pinfunction "2_2") (pintype "passive"))
    )
    (net (code "14") (name "/I2C2_SDA") (class "Default")
      (node (ref "IC2") (pin "5") (pinfunction "SDA/SI_5") (pintype "passive"))
      (node (ref "IC3") (pin "24") (pinfunction "SDA_24") (pintype "passive"))
      (node (ref "IC5") (pin "22") (pinfunction "I2C2_SDA/PB11_22") (pintype "bidirectional"))
      (node (ref "IC7") (pin "3") (pinfunction "SDI_3") (pintype "passive"))
      (node (ref "IC8") (pin "7") (pinfunction "SDA_7") (pintype "passive"))
      (node (ref "JP3") (pin "6") (pinfunction "6_6") (pintype "passive"))
      (node (ref "R11") (pin "2") (pinfunction "2_2") (pintype "passive"))
    )
    (net (code "15") (name "/I2C_SCL") (class "Default")
      (node (ref "JP1") (pin "2") (pinfunction "2_2") (pintype "passive"))
      (node (ref "Q1") (pin "3") (pinfunction "D_3") (pintype "passive"))
    )
    (net (code "16") (name "/I2C_SDA") (class "Default")
      (node (ref "JP1") (pin "1") (pinfunction "1_1") (pintype "passive"))
      (node (ref "Q2") (pin "3") (pinfunction "D_3") (pintype "passive"))
    )
    (net (code "17") (name "/IO0") (class "Default")
      (node (ref "IC6") (pin "11") (pinfunction "IO0_11") (pintype "passive"))
      (node (ref "JP2") (pin "3") (pinfunction "3_3") (pintype "passive"))
    )
    (net (code "18") (name "/KEY1") (class "Default")
      (node (ref "C30") (pin "1") (pinfunction "1_1") (pintype "passive"))
      (node (ref "IC5") (pin "16") (pinfunction "PA6/TIM3_CH1_16") (pintype "bidirectional"))
      (node (ref "K1") (pin "c") (pinfunction "c_c") (pintype "passive"))
      (node (ref "K1") (pin "d") (pinfunction "d_d") (pintype "passive"))
    )
    (net (code "19") (name "/KEY2") (class "Default")
      (node (ref "C31") (pin "1") (pinfunction "1_1") (pintype "passive"))
      (node (ref "IC5") (pin "14") (pinfunction "PA4/ADC12_IN4_14") (pintype "bidirectional"))
      (node (ref "K1") (pin "f") (pinfunction "f_f") (pintype "passive"))
      (node (ref "K1") (pin "g") (pinfunction "g_g") (pintype "passive"))
    )
    (net (code "20") (name "/KEY3") (class "Default")
      (node (ref "C40") (pin "1") (pinfunction "1_1") (pintype "passive"))
      (node (ref "IC5") (pin "15") (pinfunction "PA5/ADC12_IN5_15") (pintype "bidirectional"))
      (node (ref "K1") (pin "e") (pinfunction "e_e") (pintype "passive"))
    )
    (net (code "21") (name "/KEY4") (class "Default")
      (node (ref "DZx1") (pin "2") (pinfunction "2_2") (pintype "passive"))
      (node (ref "IC5") (pin "2") (pinfunction "PC13-TAMPER-RTC_2") (pintype "bidirectional"))
      (node (ref "R32") (pin "2") (pinfunction "2_2") (pintype "passive"))
    )
    (net (code "22") (name "/LED") (class "Default")
      (node (ref "IC5") (pin "46") (pinfunction "TIM4_CH4/PB9_46") (pintype "bidirectional"))
      (node (ref "LED1") (pin "2") (pinfunction "K_2") (pintype "passive"))
    )
    (net (code "23") (name "/MAX_INT") (class "Default")
      (node (ref "IC1") (pin "13") (pinfunction "~{INT}_13") (pintype "open_collector"))
      (node (ref "IC5") (pin "42") (pinfunction "TIM4_CH1/PB6_42") (pintype "bidirectional"))
      (node (ref "JP1") (pin "5") (pinfunction "5_5") (pintype "passive"))
      (node (ref "JP3") (pin "2") (pinfunction "2_2") (pintype "passive"))
      (node (ref "R17") (pin "1") (pinfunction "1_1") (pintype "passive"))
    )
    (net (code "24") (name "/MAX_SCL") (class "Default")
      (node (ref "IC1") (pin "2") (pinfunction "SCL_2") (pintype "bidirectional"))
      (node (ref "Q1") (pin "2") (pinfunction "S_2") (pintype "passive"))
      (node (ref "R14") (pin "2") (pinfunction "2_2") (pintype "passive"))
    )
    (net (code "25") (name "/MAX_SDA") (class "Default")
      (node (ref "IC1") (pin "3") (pinfunction "SDA_3") (pintype "bidirectional"))
      (node (ref "Q2") (pin "2") (pinfunction "S_2") (pintype "passive"))
      (node (ref "R15") (pin "2") (pinfunction "2_2") (pintype "passive"))
    )
    (net (code "26") (name "/MPU_INT") (class "Default")
      (node (ref "IC3") (pin "12") (pinfunction "INT_12") (pintype "passive"))
      (node (ref "IC5") (pin "25") (pinfunction "SPI2_NSS/PB12_25") (pintype "bidirectional"))
    )
    (net (code "27") (name "/NRST") (class "Default")
      (node (ref "C28") (pin "2") (pinfunction "2_2") (pintype "passive"))
      (node (ref "IC5") (pin "7") (pinfunction "NRST_7") (pintype "bidirectional"))
      (node (ref "R31") (pin "1") (pinfunction "1_1") (pintype "passive"))
      (node (ref "SW_RST2") (pin "1") (pinfunction "1_1") (pintype "passive"))
    )
    (net (code "28") (name "/OLED_EN") (class "Default")
      (node (ref "IC10") (pin "4") (pinfunction "SHDN#_4") (pintype "passive"))
      (node (ref "JP4") (pin "4") (pinfunction "GPIO_4") (pintype "passive"))
      (node (ref "R24") (pin "1") (pinfunction "1_1") (pintype "passive"))
    )
    (net (code "29") (name "/OLED_RES") (class "Default")
      (node (ref "C25") (pin "2") (pinfunction "2_2") (pintype "passive"))
      (node (ref "IC5") (pin "40") (pinfunction "PB4/JNTRST_40") (pintype "bidirectional"))
      (node (ref "JP4") (pin "12") (pinfunction "RES#_12") (pintype "passive"))
      (node (ref "R25") (pin "2") (pinfunction "2_2") (pintype "passive"))
    )
    (net (code "30") (name "/OSC_IN") (class "Default")
      (node (ref "C27") (pin "1") (pinfunction "1_1") (pintype "passive"))
      (node (ref "IC5") (pin "5") (pinfunction "OSC_IN/PD0_5") (pintype "input"))
      (node (ref "X1") (pin "1") (pinfunction "1_1") (pintype "passive"))
    )
    (net (code "31") (name "/OSC_OUT") (class "Default")
      (node (ref "C29") (pin "1") (pinfunction "1_1") (pintype "passive"))
      (node (ref "IC5") (pin "6") (pinfunction "OSC_OUT/PD1_6") (pintype "output"))
      (node (ref "X1") (pin "3") (pinfunction "3_3") (pintype "passive"))
    )
    (net (code "32") (name "/POWER_EN") (class "Default")
      (node (ref "IC5") (pin "43") (pinfunction "TIM4_CH2/PB7_43") (pintype "bidirectional"))
      (node (ref "R39") (pin "2") (pinfunction "2_2") (pintype "passive"))
    )
    (net (code "33") (name "/SPI2_MISO") (class "Default")
      (node (ref "IC5") (pin "27") (pinfunction "SPI2_MISO/PB14_27") (pintype "bidirectional"))
      (node (ref "IC9") (pin "2") (pinfunction "DO_2") (pintype "passive"))
      (node (ref "JP4") (pin "13") (pinfunction "DC_13") (pintype "passive"))
    )
    (net (code "34") (name "/SPI2_MOSI") (class "Default")
      (node (ref "IC5") (pin "28") (pinfunction "SPI2_MOSI/PB15_28") (pintype "bidirectional"))
      (node (ref "IC9") (pin "5") (pinfunction "DI_5") (pintype "passive"))
      (node (ref "JP4") (pin "17") (pinfunction "D1_17") (pintype "passive"))
    )
    (net (code "35") (name "/SPI2_NSS1") (class "Default")
      (node (ref "IC5") (pin "41") (pinfunction "PB5_41") (pintype "bidirectional"))
      (node (ref "JP4") (pin "11") (pinfunction "CS#_11") (pintype "passive"))
    )
    (net (code "36") (name "/SPI2_NSS2") (class "Default")
      (node (ref "IC5") (pin "38") (pinfunction "PA15/JTDI_38") (pintype "bidirectional"))
      (node (ref "IC9") (pin "1") (pinfunction "~{CS}_1") (pintype "passive"))
      (node (ref "R13") (pin "1") (pinfunction "1_1") (pintype "passive"))
    )
    (net (code "37") (name "/SPI2_SCK") (class "Default")
      (node (ref "IC5") (pin "26") (pinfunction "SPI2_SCK/PB13_26") (pintype "bidirectional"))
      (node (ref "IC9") (pin "6") (pinfunction "CLK_6") (pintype "passive"))
      (node (ref "JP4") (pin "16") (pinfunction "D0_16") (pintype "passive"))
    )
    (net (code "38") (name "/STDBY") (class "Default")
      (node (ref "IC11") (pin "7") (pinfunction "CHRG#_7") (pintype "passive"))
      (node (ref "IC5") (pin "33") (pinfunction "PA12/USBDP_33") (pintype "bidirectional"))
      (node (ref "R22") (pin "1") (pinfunction "1_1") (pintype "passive"))
    )
    (net (code "39") (name "/SWCLK") (class "Default")
      (node (ref "IC5") (pin "37") (pinfunction "PA14/JTCK/SWCLK_37") (pintype "bidirectional"))
      (node (ref "JP5") (pin "2") (pinfunction "2_2") (pintype "passive"))
    )
    (net (code "40") (name "/SWDIO") (class "Default")
      (node (ref "IC5") (pin "34") (pinfunction "PA13/JTMS/SWDIO_34") (pintype "bidirectional"))
      (node (ref "JP5") (pin "3") (pinfunction "3_3") (pintype "passive"))
    )
    (net (code "41") (name "/USART1_RX") (class "Default")
      (node (ref "IC5") (pin "31") (pinfunction "PA10/USART1_RX_31") (pintype "bidirectional"))
      (node (ref "JP5") (pin "4") (pinfunction "4_4") (pintype "passive"))
    )
    (net (code "42") (name "/USART1_TX") (class "Default")
      (node (ref "IC5") (pin "30") (pinfunction "PA9/USART1_TX_30") (pintype "bidirectional"))
      (node (ref "JP5") (pin "5") (pinfunction "5_5") (pintype "passive"))
    )
    (net (code "43") (name "BAT+") (class "Default")
      (node (ref "C26") (pin "1") (pinfunction "1_1") (pintype "passive"))
      (node (ref "H1") (pin "+") (pinfunction "+_+") (pintype "passive"))
      (node (ref "IC11") (pin "5") (pinfunction "BAT_5") (pintype "passive"))
      (node (ref "Q3") (pin "3") (pinfunction "D_3") (pintype "passive"))
      (node (ref "R2") (pin "2") (pinfunction "2_2") (pintype "passive"))
    )
    (net (code "44") (name "BAT-") (class "Default")
      (node (ref "C4") (pin "1") (pinfunction "1_1") (pintype "passive"))
      (node (ref "H1") (pin "-") (pinfunction "-_-") (pintype "passive"))
      (node (ref "IC4") (pin "1") (pinfunction "OVD_1") (pintype "passive"))
      (node (ref "IC4") (pin "5") (pinfunction "IS1_5") (pintype "passive"))
      (node (ref "IC4") (pin "6") (pinfunction "VSS_6") (pintype "passive"))
      (node (ref "R5") (pin "1") (pinfunction "1_1") (pintype "passive"))
    )
    (net (code "45") (name "GND") (class "Default")
      (node (ref "C1") (pin "2") (pinfunction "2_2") (pintype "passive"))
      (node (ref "C10") (pin "1") (pinfunction "1_1") (pintype "passive"))
      (node (ref "C11") (pin "2") (pinfunction "2_2") (pintype "passive"))
      (node (ref "C12") (pin "2") (pinfunction "2_2") (pintype "passive"))
      (node (ref "C13") (pin "2") (pinfunction "2_2") (pintype "passive"))
      (node (ref "C14") (pin "1") (pinfunction "1_1") (pintype "passive"))
      (node (ref "C15") (pin "1") (pinfunction "1_1") (pintype "passive"))
      (node (ref "C16") (pin "1") (pinfunction "1_1") (pintype "passive"))
      (node (ref "C17") (pin "1") (pinfunction "1_1") (pintype "passive"))
      (node (ref "C18") (pin "1") (pinfunction "1_1") (pintype "passive"))
      (node (ref "C19") (pin "1") (pinfunction "1_1") (pintype "passive"))
      (node (ref "C2") (pin "2") (pinfunction "2_2") (pintype "passive"))
      (node (ref "C20") (pin "1") (pinfunction "1_1") (pintype "passive"))
      (node (ref "C22") (pin "1") (pinfunction "1_1") (pintype "passive"))
      (node (ref "C23") (pin "1") (pinfunction "1_1") (pintype "passive"))
      (node (ref "C24") (pin "1") (pinfunction "1_1") (pintype "passive"))
      (node (ref "C25") (pin "1") (pinfunction "1_1") (pintype "passive"))
      (node (ref "C26") (pin "2") (pinfunction "2_2") (pintype "passive"))
      (node (ref "C27") (pin "2") (pinfunction "2_2") (pintype "passive"))
      (node (ref "C28") (pin "1") (pinfunction "1_1") (pintype "passive"))
      (node (ref "C29") (pin "2") (pinfunction "2_2") (pintype "passive"))
      (node (ref "C3") (pin "1") (pinfunction "1_1") (pintype "passive"))
      (node (ref "C30") (pin "2") (pinfunction "2_2") (pintype "passive"))
      (node (ref "C31") (pin "2") (pinfunction "2_2") (pintype "passive"))
      (node (ref "C32") (pin "2") (pinfunction "2_2") (pintype "passive"))
      (node (ref "C33") (pin "2") (pinfunction "2_2") (pintype "passive"))
      (node (ref "C34") (pin "2") (pinfunction "2_2") (pintype "passive"))
      (node (ref "C35") (pin "2") (pinfunction "2_2") (pintype "passive"))
      (node (ref "C36") (pin "1") (pinfunction "1_1") (pintype "passive"))
      (node (ref "C38") (pin "1") (pinfunction "1_1") (pintype "passive"))
      (node (ref "C39") (pin "2") (pinfunction "2_2") (pintype "passive"))
      (node (ref "C40") (pin "2") (pinfunction "2_2") (pintype "passive"))
      (node (ref "C5") (pin "2") (pinfunction "2_2") (pintype "passive"))
      (node (ref "C6") (pin "1") (pinfunction "1_1") (pintype "passive"))
      (node (ref "C7") (pin "2") (pinfunction "2_2") (pintype "passive"))
      (node (ref "C8") (pin "1") (pinfunction "1_1") (pintype "passive"))
      (node (ref "C9") (pin "1") (pinfunction "1_1") (pintype "passive"))
      (node (ref "E1") (pin "2") (pinfunction "K_2") (pintype "passive"))
      (node (ref "E2") (pin "2") (pinfunction "K_2") (pintype "passive"))
      (node (ref "E3") (pin "2") (pinfunction "K_2") (pintype "passive"))
      (node (ref "E4") (pin "2") (pinfunction "K_2") (pintype "passive"))
      (node (ref "IC1") (pin "4") (pinfunction "PGND_4") (pintype "power_in"))
      (node (ref "IC10") (pin "2") (pinfunction "GND_2") (pintype "passive"))
      (node (ref "IC11") (pin "1") (pinfunction "TEMP_1") (pintype "passive"))
      (node (ref "IC11") (pin "3") (pinfunction "GND_3") (pintype "passive"))
      (node (ref "IC12") (pin "2") (pinfunction "GND_2") (pintype "passive"))
      (node (ref "IC13") (pin "2") (pinfunction "GND_2") (pintype "passive"))
      (node (ref "IC14") (pin "1") (pinfunction "GND_1") (pintype "passive"))
      (node (ref "IC2") (pin "11") (pinfunction "CAD1_11") (pintype "passive"))
      (node (ref "IC2") (pin "13") (pinfunction "CAD0_13") (pintype "passive"))
      (node (ref "IC2") (pin "15") (pinfunction "VSS_15") (pintype "passive"))
      (node (ref "IC3") (pin "18") (pinfunction "GND_18") (pintype "passive"))
      (node (ref "IC4") (pin "4") (pinfunction "IS2_4") (pintype "passive"))
      (node (ref "IC5") (pin "20") (pinfunction "PB2/BOOT1_20") (pintype "bidirectional"))
      (node (ref "IC5") (pin "23") (pinfunction "VSS_1_23") (pintype "power_in"))
      (node (ref "IC5") (pin "35") (pinfunction "VSS_2_35") (pintype "power_in"))
      (node (ref "IC5") (pin "44") (pinfunction "BOOT0_44") (pintype "bidirectional"))
      (node (ref "IC5") (pin "47") (pinfunction "VSS_3_47") (pintype "power_in"))
      (node (ref "IC5") (pin "8") (pinfunction "VSSA_8") (pintype "power_in"))
      (node (ref "IC6") (pin "18") (pinfunction "GND_18") (pintype "passive"))
      (node (ref "IC6") (pin "19") (pinfunction "GND_19") (pintype "passive"))
      (node (ref "IC6") (pin "2") (pinfunction "GND_2") (pintype "passive"))
      (node (ref "IC7") (pin "1") (pinfunction "GND_1") (pintype "passive"))
      (node (ref "IC7") (pin "7") (pinfunction "GND_7") (pintype "passive"))
      (node (ref "IC8") (pin "5") (pinfunction "GND_5") (pintype "passive"))
      (node (ref "IC9") (pin "4") (pinfunction "GND_4") (pintype "passive"))
      (node (ref "JP1") (pin "6") (pinfunction "6_6") (pintype "passive"))
      (node (ref "JP3") (pin "1") (pinfunction "1_1") (pintype "passive"))
      (node (ref "JP4") (pin "1") (pinfunction "VSS_1") (pintype "passive"))
      (node (ref "JP4") (pin "14") (pinfunction "WR_14") (pintype "passive"))
      (node (ref "JP4") (pin "15") (pinfunction "RD_15") (pintype "passive"))
      (node (ref "JP4") (pin "19") (pinfunction "D3_19") (pintype "passive"))
      (node (ref "JP4") (pin "20") (pinfunction "D4_20") (pintype "passive"))
      (node (ref "JP4") (pin "21") (pinfunction "D5_21") (pintype "passive"))
      (node (ref "JP4") (pin "22") (pinfunction "D6_22") (pintype "passive"))
      (node (ref "JP4") (pin "23") (pinfunction "D7_23") (pintype "passive"))
      (node (ref "JP4") (pin "25") (pinfunction "VSS_25") (pintype "passive"))
      (node (ref "JP4") (pin "7") (pinfunction "BS1_7") (pintype "passive"))
      (node (ref "JP4") (pin "8") (pinfunction "BS2_8") (pintype "passive"))
      (node (ref "JP4") (pin "9") (pinfunction "VSS_9") (pintype "passive"))
      (node (ref "JP5") (pin "1") (pinfunction "1_1") (pintype "passive"))
      (node (ref "K1") (pin "a") (pinfunction "a_a") (pintype "passive"))
      (node (ref "Q5") (pin "2") (pinfunction "E_2") (pintype "passive"))
      (node (ref "Q6") (pin "2") (pinfunction "E_2") (pintype "passive"))
      (node (ref "R16") (pin "1") (pinfunction "1_1") (pintype "passive"))
      (node (ref "R26") (pin "1") (pinfunction "1_1") (pintype "passive"))
      (node (ref "R27") (pin "1") (pinfunction "1_1") (pintype "passive"))
      (node (ref "R29") (pin "1") (pinfunction "1_1") (pintype "passive"))
      (node (ref "R3") (pin "2") (pinfunction "2_2") (pintype "passive"))
      (node (ref "R30") (pin "2") (pinfunction "2_2") (pintype "passive"))
      (node (ref "R37") (pin "1") (pinfunction "1_1") (pintype "passive"))
      (node (ref "R4") (pin "1") (pinfunction "1_1") (pintype "passive"))
      (node (ref "R40") (pin "1") (pinfunction "1_1") (pintype "passive"))
      (node (ref "R5") (pin "2") (pinfunction "2_2") (pintype "passive"))
      (node (ref "SW_PWR1") (pin "2") (pinfunction "2_2") (pintype "passive"))
      (node (ref "SW_RST1") (pin "2") (pinfunction "2_2") (pintype "passive"))
      (node (ref "SW_RST2") (pin "2") (pinfunction "2_2") (pintype "passive"))
      (node (ref "USB1") (pin "A12") (pinfunction "GND_A12") (pintype "passive"))
      (node (ref "USB1") (pin "B12") (pinfunction "GND_B12") (pintype "passive"))
      (node (ref "X1") (pin "2") (pinfunction "2_2") (pintype "passive"))
      (node (ref "X1") (pin "4") (pinfunction "4_4") (pintype "passive"))
    )
    (net (code "46") (name "Net-(BUZZER1--)") (class "Default")
      (node (ref "BUZZER1") (pin "2") (pinfunction "-_2") (pintype "passive"))
      (node (ref "Q5") (pin "3") (pinfunction "C_3") (pintype "passive"))
    )
    (net (code "47") (name "Net-(C36-Pad2)") (class "Default")
      (node (ref "C36") (pin "2") (pinfunction "2_2") (pintype "passive"))
      (node (ref "DZx1") (pin "3") (pinfunction "3_3") (pintype "passive"))
      (node (ref "SW_PWR1") (pin "1") (pinfunction "1_1") (pintype "passive"))
    )
    (net (code "48") (name "Net-(D1-A)") (class "Default")
      (node (ref "D1") (pin "1") (pinfunction "A_1") (pintype "passive"))
      (node (ref "IC10") (pin "1") (pinfunction "SW_1") (pintype "passive"))
      (node (ref "L1") (pin "2") (pinfunction "2_2") (pintype "passive"))
    )
    (net (code "49") (name "Net-(E3-A)") (class "Default")
      (node (ref "E3") (pin "1") (pinfunction "A_1") (pintype "passive"))
      (node (ref "JP4") (pin "3") (pinfunction "VCOMH_3") (pintype "passive"))
    )
    (net (code "50") (name "Net-(IC1-GND)") (class "Default")
      (node (ref "IC1") (pin "12") (pinfunction "GND_12") (pintype "power_in"))
      (node (ref "R4") (pin "2") (pinfunction "2_2") (pintype "passive"))
    )
    (net (code "51") (name "Net-(IC3-AD0)") (class "Default")
      (node (ref "IC3") (pin "9") (pinfunction "AD0_9") (pintype "passive"))
      (node (ref "R3") (pin "1") (pinfunction "1_1") (pintype "passive"))
    )
    (net (code "52") (name "Net-(IC3-CPOUT)") (class "Default")
      (node (ref "C6") (pin "2") (pinfunction "2_2") (pintype "passive"))
      (node (ref "IC3") (pin "20") (pinfunction "CPOUT_20") (pintype "passive"))
    )
    (net (code "53") (name "Net-(IC3-REGOUT)") (class "Default")
      (node (ref "C7") (pin "1") (pinfunction "1_1") (pintype "passive"))
      (node (ref "IC3") (pin "10") (pinfunction "REGOUT_10") (pintype "passive"))
    )
    (net (code "54") (name "Net-(IC3-VLOGIC)") (class "Default")
      (node (ref "C2") (pin "1") (pinfunction "1_1") (pintype "passive"))
      (node (ref "IC3") (pin "8") (pinfunction "VLOGIC_8") (pintype "passive"))
    )
    (net (code "55") (name "Net-(IC4-VDD)") (class "Default")
      (node (ref "C4") (pin "2") (pinfunction "2_2") (pintype "passive"))
      (node (ref "IC4") (pin "8") (pinfunction "VDD_8") (pintype "passive"))
      (node (ref "R2") (pin "1") (pinfunction "1_1") (pintype "passive"))
    )
    (net (code "56") (name "Net-(IC7-CSB)") (class "Default")
      (node (ref "IC7") (pin "2") (pinfunction "CSB_2") (pintype "passive"))
      (node (ref "R12") (pin "1") (pinfunction "1_1") (pintype "passive"))
    )
    (net (code "57") (name "Net-(IC7-SDO)") (class "Default")
      (node (ref "IC7") (pin "5") (pinfunction "SDO_5") (pintype "passive"))
      (node (ref "R16") (pin "2") (pinfunction "2_2") (pintype "passive"))
    )
    (net (code "58") (name "Net-(IC8-32KHz)") (class "Default")
      (node (ref "IC8") (pin "1") (pinfunction "32KHz_1") (pintype "passive"))
      (node (ref "R7") (pin "2") (pinfunction "2_2") (pintype "passive"))
    )
    (net (code "59") (name "Net-(IC10-FB)") (class "Default")
      (node (ref "C21") (pin "1") (pinfunction "1_1") (pintype "passive"))
      (node (ref "IC10") (pin "3") (pinfunction "FB_3") (pintype "passive"))
      (node (ref "R21") (pin "1") (pinfunction "1_1") (pintype "passive"))
      (node (ref "R27") (pin "2") (pinfunction "2_2") (pintype "passive"))
    )
    (net (code "60") (name "Net-(IC11-CE)") (class "Default")
      (node (ref "IC11") (pin "8") (pinfunction "CE_8") (pintype "passive"))
      (node (ref "R19") (pin "1") (pinfunction "1_1") (pintype "passive"))
    )
    (net (code "61") (name "Net-(IC11-PROG)") (class "Default")
      (node (ref "IC11") (pin "2") (pinfunction "PROG_2") (pintype "passive"))
      (node (ref "R29") (pin "2") (pinfunction "2_2") (pintype "passive"))
    )
    (net (code "62") (name "Net-(IC11-VCC)") (class "Default")
      (node (ref "C23") (pin "2") (pinfunction "2_2") (pintype "passive"))
      (node (ref "IC11") (pin "4") (pinfunction "VCC_4") (pintype "passive"))
      (node (ref "R20") (pin "1") (pinfunction "1_1") (pintype "passive"))
    )
    (net (code "63") (name "Net-(IC12-C+)") (class "Default")
      (node (ref "C37") (pin "1") (pinfunction "1_1") (pintype "passive"))
      (node (ref "IC12") (pin "6") (pinfunction "C+_6") (pintype "passive"))
    )
    (net (code "64") (name "Net-(IC12-C-)") (class "Default")
      (node (ref "C37") (pin "2") (pinfunction "2_2") (pintype "passive"))
      (node (ref "IC12") (pin "4") (pinfunction "C-_4") (pintype "passive"))
    )
    (net (code "65") (name "Net-(JP4-IREF)") (class "Default")
      (node (ref "JP4") (pin "10") (pinfunction "IREF_10") (pintype "passive"))
      (node (ref "R26") (pin "2") (pinfunction "2_2") (pintype "passive"))
    )
    (net (code "66") (name "Net-(JP4-VDD)") (class "Default")
      (node (ref "C22") (pin "2") (pinfunction "2_2") (pintype "passive"))
      (node (ref "JP4") (pin "6") (pinfunction "VDD_6") (pintype "passive"))
    )
    (net (code "67") (name "Net-(LED1-A)") (class "Default")
      (node (ref "LED1") (pin "1") (pinfunction "A_1") (pintype "passive"))
      (node (ref "R18") (pin "1") (pinfunction "1_1") (pintype "passive"))
    )
    (net (code "68") (name "Net-(Q4-G)") (class "Default")
      (node (ref "DZx1") (pin "1") (pinfunction "1_1") (pintype "passive"))
      (node (ref "Q4") (pin "1") (pinfunction "G_1") (pintype "passive"))
      (node (ref "Q6") (pin "3") (pinfunction "C_3") (pintype "passive"))
      (node (ref "R38") (pin "2") (pinfunction "2_2") (pintype "passive"))
    )
    (net (code "69") (name "Net-(Q5-B)") (class "Default")
      (node (ref "Q5") (pin "1") (pinfunction "B_1") (pintype "passive"))
      (node (ref "R35") (pin "2") (pinfunction "2_2") (pintype "passive"))
      (node (ref "R37") (pin "2") (pinfunction "2_2") (pintype "passive"))
    )
    (net (code "70") (name "Net-(Q6-B)") (class "Default")
      (node (ref "Q6") (pin "1") (pinfunction "B_1") (pintype "passive"))
      (node (ref "R39") (pin "1") (pinfunction "1_1") (pintype "passive"))
      (node (ref "R40") (pin "2") (pinfunction "2_2") (pintype "passive"))
    )
    (net (code "71") (name "VBUS") (class "Default")
      (node (ref "D2") (pin "1") (pinfunction "A_1") (pintype "passive"))
      (node (ref "Q3") (pin "1") (pinfunction "G_1") (pintype "passive"))
      (node (ref "R19") (pin "2") (pinfunction "2_2") (pintype "passive"))
      (node (ref "R20") (pin "2") (pinfunction "2_2") (pintype "passive"))
      (node (ref "R30") (pin "1") (pinfunction "1_1") (pintype "passive"))
      (node (ref "USB1") (pin "A9") (pinfunction "VBUS_A9") (pintype "passive"))
      (node (ref "USB1") (pin "B9") (pinfunction "VBUS_B9") (pintype "passive"))
    )
    (net (code "72") (name "VLOUD") (class "Default")
      (node (ref "C24") (pin "2") (pinfunction "2_2") (pintype "passive"))
      (node (ref "C32") (pin "1") (pinfunction "1_1") (pintype "passive"))
      (node (ref "C34") (pin "1") (pinfunction "1_1") (pintype "passive"))
      (node (ref "C38") (pin "2") (pinfunction "2_2") (pintype "passive"))
      (node (ref "IC10") (pin "5") (pinfunction "VIN_5") (pintype "passive"))
      (node (ref "IC12") (pin "3") (pinfunction "EN_3") (pintype "passive"))
      (node (ref "IC12") (pin "5") (pinfunction "VIN_5") (pintype "passive"))
      (node (ref "IC13") (pin "1") (pinfunction "VIN_1") (pintype "passive"))
      (node (ref "IC13") (pin "3") (pinfunction "EN_3") (pintype "passive"))
      (node (ref "IC14") (pin "3") (pinfunction "VIN_3") (pintype "passive"))
      (node (ref "L1") (pin "1") (pinfunction "1_1") (pintype "passive"))
      (node (ref "Q4") (pin "3") (pinfunction "D_3") (pintype "passive"))
      (node (ref "R24") (pin "2") (pinfunction "2_2") (pintype "passive"))
      (node (ref "R32") (pin "1") (pinfunction "1_1") (pintype "passive"))
    )
    (net (code "73") (name "VOUT") (class "Default")
      (node (ref "D2") (pin "2") (pinfunction "K_2") (pintype "passive"))
      (node (ref "E4") (pin "1") (pinfunction "A_1") (pintype "passive"))
      (node (ref "IC8") (pin "6") (pinfunction "VBAT_6") (pintype "passive"))
      (node (ref "Q3") (pin "2") (pinfunction "S_2") (pintype "passive"))
      (node (ref "Q4") (pin "2") (pinfunction "S_2") (pintype "passive"))
      (node (ref "R38") (pin "1") (pinfunction "1_1") (pintype "passive"))
    )
    (net (code "74") (name "unconnected-(IC1-NC-Pad1)") (class "Default")
      (node (ref "IC1") (pin "1") (pinfunction "NC_1") (pintype "passive"))
    )
    (net (code "75") (name "unconnected-(IC1-NC-Pad5)") (class "Default")
      (node (ref "IC1") (pin "5") (pinfunction "NC_5") (pintype "passive"))
    )
    (net (code "76") (name "unconnected-(IC1-NC-Pad6)") (class "Default")
      (node (ref "IC1") (pin "6") (pinfunction "NC_6") (pintype "passive"))
    )
    (net (code "77") (name "unconnected-(IC1-NC-Pad7)") (class "Default")
      (node (ref "IC1") (pin "7") (pinfunction "NC_7") (pintype "passive"))
    )
    (net (code "78") (name "unconnected-(IC1-NC-Pad8)") (class "Default")
      (node (ref "IC1") (pin "8") (pinfunction "NC_8") (pintype "passive"))
    )
    (net (code "79") (name "unconnected-(IC1-NC-Pad14)") (class "Default")
      (node (ref "IC1") (pin "14") (pinfunction "NC_14") (pintype "passive"))
    )
    (net (code "80") (name "unconnected-(IC2-NC1-Pad8)") (class "Default")
      (node (ref "IC2") (pin "8") (pinfunction "NC1_8") (pintype "passive"))
    )
    (net (code "81") (name "unconnected-(IC2-NC2-Pad12)") (class "Default")
      (node (ref "IC2") (pin "12") (pinfunction "NC2_12") (pintype "passive"))
    )
    (net (code "82") (name "unconnected-(IC2-RSV-Pad3)") (class "Default")
      (node (ref "IC2") (pin "3") (pinfunction "RSV_3") (pintype "passive"))
    )
    (net (code "83") (name "unconnected-(IC2-SO-Pad6)") (class "Default")
      (node (ref "IC2") (pin "6") (pinfunction "SO_6") (pintype "passive"))
    )
    (net (code "84") (name "unconnected-(IC2-TST1-Pad1)") (class "Default")
      (node (ref "IC2") (pin "1") (pinfunction "TST1_1") (pintype "passive"))
    )
    (net (code "85") (name "unconnected-(IC2-TST2-Pad14)") (class "Default")
      (node (ref "IC2") (pin "14") (pinfunction "TST2_14") (pintype "passive"))
    )
    (net (code "86") (name "unconnected-(IC2-TST6-Pad9)") (class "Default")
      (node (ref "IC2") (pin "9") (pinfunction "TST6_9") (pintype "passive"))
    )
    (net (code "87") (name "unconnected-(IC3-AUX_CL-Pad7)") (class "Default")
      (node (ref "IC3") (pin "7") (pinfunction "AUX_CL_7") (pintype "passive"))
    )
    (net (code "88") (name "unconnected-(IC3-AUX_DA-Pad6)") (class "Default")
      (node (ref "IC3") (pin "6") (pinfunction "AUX_DA_6") (pintype "passive"))
    )
    (net (code "89") (name "unconnected-(IC3-CLKIN-Pad1)") (class "Default")
      (node (ref "IC3") (pin "1") (pinfunction "CLKIN_1") (pintype "passive"))
    )
    (net (code "90") (name "unconnected-(IC3-CLKOUT-Pad22)") (class "Default")
      (node (ref "IC3") (pin "22") (pinfunction "CLKOUT_22") (pintype "passive"))
    )
    (net (code "91") (name "unconnected-(IC3-FSYNC-Pad11)") (class "Default")
      (node (ref "IC3") (pin "11") (pinfunction "FSYNC_11") (pintype "passive"))
    )
    (net (code "92") (name "unconnected-(IC3-RESV-Pad19)") (class "Default")
      (node (ref "IC3") (pin "19") (pinfunction "RESV_19") (pintype "passive"))
    )
    (net (code "93") (name "unconnected-(IC3-RESV-Pad21)") (class "Default")
      (node (ref "IC3") (pin "21") (pinfunction "RESV_21") (pintype "passive"))
    )
    (net (code "94") (name "unconnected-(IC4-PIO-Pad2)") (class "Default")
      (node (ref "IC4") (pin "2") (pinfunction "PIO_2") (pintype "passive"))
    )
    (net (code "95") (name "unconnected-(IC4-SNS-Pad3)") (class "Default")
      (node (ref "IC4") (pin "3") (pinfunction "SNS_3") (pintype "passive"))
    )
    (net (code "96") (name "unconnected-(IC5-PA8{slash}TIM1_CH1-Pad29)") (class "Default")
      (node (ref "IC5") (pin "29") (pinfunction "PA8/TIM1_CH1_29") (pintype "bidirectional"))
    )
    (net (code "97") (name "unconnected-(IC5-PC14-OSC32_IN-Pad3)") (class "Default")
      (node (ref "IC5") (pin "3") (pinfunction "PC14-OSC32_IN_3") (pintype "bidirectional"))
    )
    (net (code "98") (name "unconnected-(IC5-PC15-OSC32_OUT-Pad4)") (class "Default")
      (node (ref "IC5") (pin "4") (pinfunction "PC15-OSC32_OUT_4") (pintype "bidirectional"))
    )
    (net (code "99") (name "unconnected-(IC5-TIM3_CH3{slash}PB0-Pad18)") (class "Default")
      (node (ref "IC5") (pin "18") (pinfunction "TIM3_CH3/PB0_18") (pintype "bidirectional"))
    )
    (net (code "100") (name "unconnected-(IC5-TIM4_CH3{slash}PB8-Pad45)") (class "Default")
      (node (ref "IC5") (pin "45") (pinfunction "TIM4_CH3/PB8_45") (pintype "bidirectional"))
    )
    (net (code "101") (name "unconnected-(IC6-ADC-Pad3)") (class "Default")
      (node (ref "IC6") (pin "3") (pinfunction "ADC_3") (pintype "passive"))
    )
    (net (code "102") (name "unconnected-(IC6-ANT-Pad1)") (class "Default")
      (node (ref "IC6") (pin "1") (pinfunction "ANT_1") (pintype "passive"))
    )
    (net (code "103") (name "unconnected-(IC6-EN-Pad4)") (class "Default")
      (node (ref "IC6") (pin "4") (pinfunction "EN_4") (pintype "passive"))
    )
    (net (code "104") (name "unconnected-(IC6-IO2-Pad10)") (class "Default")
      (node (ref "IC6") (pin "10") (pinfunction "IO2_10") (pintype "passive"))
    )
    (net (code "105") (name "unconnected-(IC6-IO4-Pad12)") (class "Default")
      (node (ref "IC6") (pin "12") (pinfunction "IO4_12") (pintype "passive"))
    )
    (net (code "106") (name "unconnected-(IC6-IO5-Pad13)") (class "Default")
      (node (ref "IC6") (pin "13") (pinfunction "IO5_13") (pintype "passive"))
    )
    (net (code "107") (name "unconnected-(IC6-IO12-Pad7)") (class "Default")
      (node (ref "IC6") (pin "7") (pinfunction "IO12_7") (pintype "passive"))
    )
    (net (code "108") (name "unconnected-(IC6-IO13-Pad8)") (class "Default")
      (node (ref "IC6") (pin "8") (pinfunction "IO13_8") (pintype "passive"))
    )
    (net (code "109") (name "unconnected-(IC6-IO14-Pad6)") (class "Default")
      (node (ref "IC6") (pin "6") (pinfunction "IO14_6") (pintype "passive"))
    )
    (net (code "110") (name "unconnected-(IC6-IO15-Pad9)") (class "Default")
      (node (ref "IC6") (pin "9") (pinfunction "IO15_9") (pintype "passive"))
    )
    (net (code "111") (name "unconnected-(IC6-IO16-Pad5)") (class "Default")
      (node (ref "IC6") (pin "5") (pinfunction "IO16_5") (pintype "passive"))
    )
    (net (code "112") (name "unconnected-(IC8-RST#-Pad4)") (class "Default")
      (node (ref "IC8") (pin "4") (pinfunction "RST#_4") (pintype "passive"))
    )
    (net (code "113") (name "unconnected-(IC13-NC-Pad4)") (class "Default")
      (node (ref "IC13") (pin "4") (pinfunction "NC_4") (pintype "passive"))
    )
    (net (code "114") (name "unconnected-(JP4-D2-Pad18)") (class "Default")
      (node (ref "JP4") (pin "18") (pinfunction "D2_18") (pintype "passive"))
    )
    (net (code "115") (name "unconnected-(USB1-CC1-PadA5)") (class "Default")
      (node (ref "USB1") (pin "A5") (pinfunction "CC1_A5") (pintype "passive"))
    )
    (net (code "116") (name "unconnected-(USB1-CC2-PadB5)") (class "Default")
      (node (ref "USB1") (pin "B5") (pinfunction "CC2_B5") (pintype "passive"))
    )
  )
)
